# NFC_Snoopie_2024-06-25.net
KiCad netlist of a schematic drawn in EasyEDA Pro
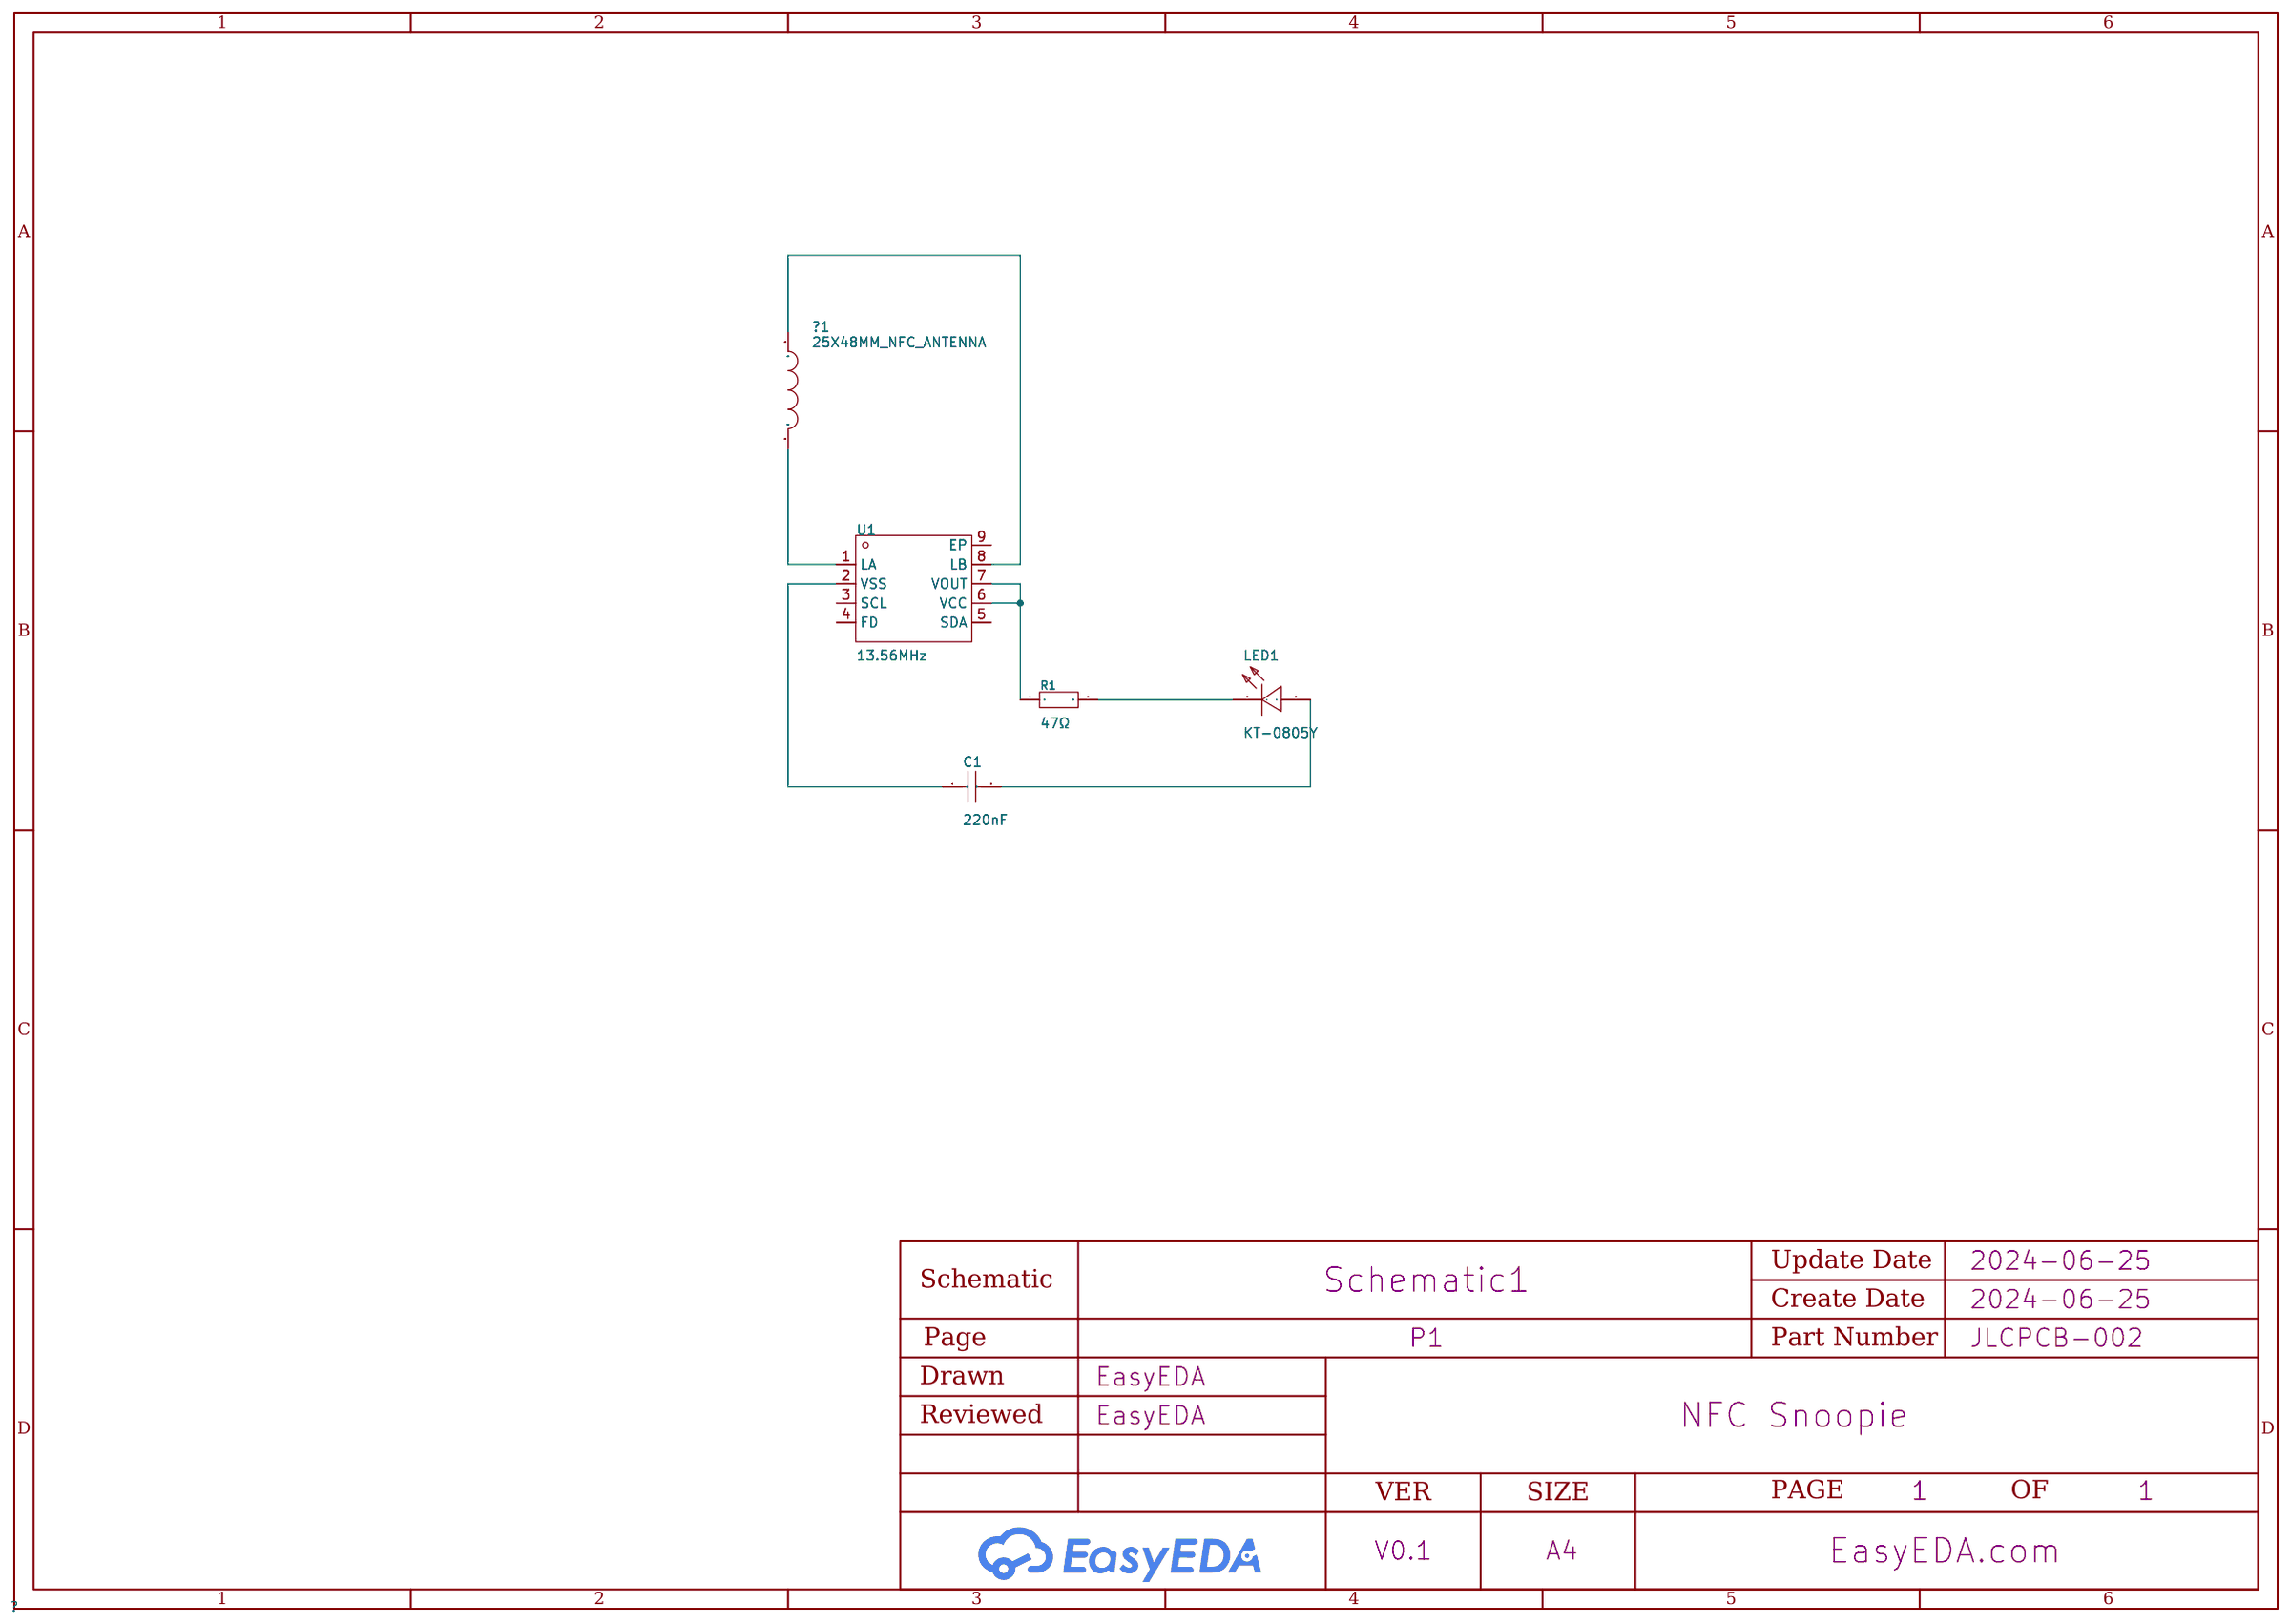
[diagram p0: schematic sheet]

(export (version "E")
  (design (tool "Eeschema 10.0.6"))
  (components
    (comp (ref "?1")
      (value "25X48MM_NFC_ANTENNA")
      (libsource (lib "easyedapro") (part "25X48MM_NFC_ANTENNA"))
    )
    (comp (ref "C1")
      (value "220nF")
      (footprint "easyedapro:C0603")
      (fields
        (field (name "Manufacturer Part") "CL10B224KA8NNNC")
        (field (name "Manufacturer") "SAMSUNG(三星)")
      )
      (libsource (lib "easyedapro") (part "CL10B224KA8NNNC"))
    )
    (comp (ref "LED1")
      (value "KT-0805Y")
      (footprint "easyedapro:LED0805-R-RD")
      (fields (field (name "Manufacturer") "KENTO"))
      (libsource (lib "easyedapro") (part "17-21SUYC/TR8"))
    )
    (comp (ref "R1")
      (value "47Ω")
      (footprint "easyedapro:R0603")
      (fields
        (field (name "Manufacturer Part") "0603WAF470JT5E")
        (field (name "Manufacturer") "UNI-ROYAL(厚声)")
      )
      (libsource (lib "easyedapro") (part "0603WAF470JT5E"))
    )
    (comp (ref "U1")
      (value "13.56MHz")
      (footprint "easyedapro:XQFN-8_L1.6-W1.6-P0.50-BL")
      (fields (field (name "Manufacturer Part") "NT3H2111W0FHKH") (field (name "Manufacturer") "NXP(恩智浦)"))
      (libsource (lib "easyedapro") (part "NT3H2111W0FHKH"))
    )
  )
  (nets
    (net (code "1") (name "Net-(LED1-+)") (class "Default")
      (node (ref "C1") (pin "2") (pinfunction "2_2") (pintype "input"))
      (node (ref "LED1") (pin "1") (pinfunction "+_1") (pintype "unspecified"))
    )
    (net (code "2") (name "Net-(LED1--)") (class "Default")
      (node (ref "LED1") (pin "2") (pinfunction "-_2") (pintype "unspecified"))
      (node (ref "R1") (pin "2") (pinfunction "2_2") (pintype "input"))
    )
    (net (code "3") (name "Net-(U1-LA)") (class "Default")
      (node (ref "?1") (pin "P$2") (pinfunction "P$2_P$2") (pintype "bidirectional"))
      (node (ref "U1") (pin "1") (pinfunction "LA_1") (pintype "unspecified"))
    )
    (net (code "4") (name "Net-(U1-LB)") (class "Default")
      (node (ref "?1") (pin "P$1") (pinfunction "P$1_P$1") (pintype "bidirectional"))
      (node (ref "U1") (pin "8") (pinfunction "LB_8") (pintype "unspecified"))
    )
    (net (code "5") (name "Net-(U1-VCC)") (class "Default")
      (node (ref "R1") (pin "1") (pinfunction "1_1") (pintype "input"))
      (node (ref "U1") (pin "6") (pinfunction "VCC_6") (pintype "unspecified"))
      (node (ref "U1") (pin "7") (pinfunction "VOUT_7") (pintype "unspecified"))
    )
    (net (code "6") (name "Net-(U1-VSS)") (class "Default")
      (node (ref "C1") (pin "1") (pinfunction "1_1") (pintype "input"))
      (node (ref "U1") (pin "2") (pinfunction "VSS_2") (pintype "unspecified"))
    )
    (net (code "7") (name "unconnected-(U1-EP-Pad9)") (class "Default")
      (node (ref "U1") (pin "9") (pinfunction "EP_9") (pintype "unspecified"))
    )
    (net (code "8") (name "unconnected-(U1-FD-Pad4)") (class "Default")
      (node (ref "U1") (pin "4") (pinfunction "FD_4") (pintype "unspecified"))
    )
    (net (code "9") (name "unconnected-(U1-SCL-Pad3)") (class "Default")
      (node (ref "U1") (pin "3") (pinfunction "SCL_3") (pintype "unspecified"))
    )
    (net (code "10") (name "unconnected-(U1-SDA-Pad5)") (class "Default")
      (node (ref "U1") (pin "5") (pinfunction "SDA_5") (pintype "unspecified"))
    )
  )
)
